# BAR30-SENSOR.net
KiCad netlist of a schematic drawn in EAGLE
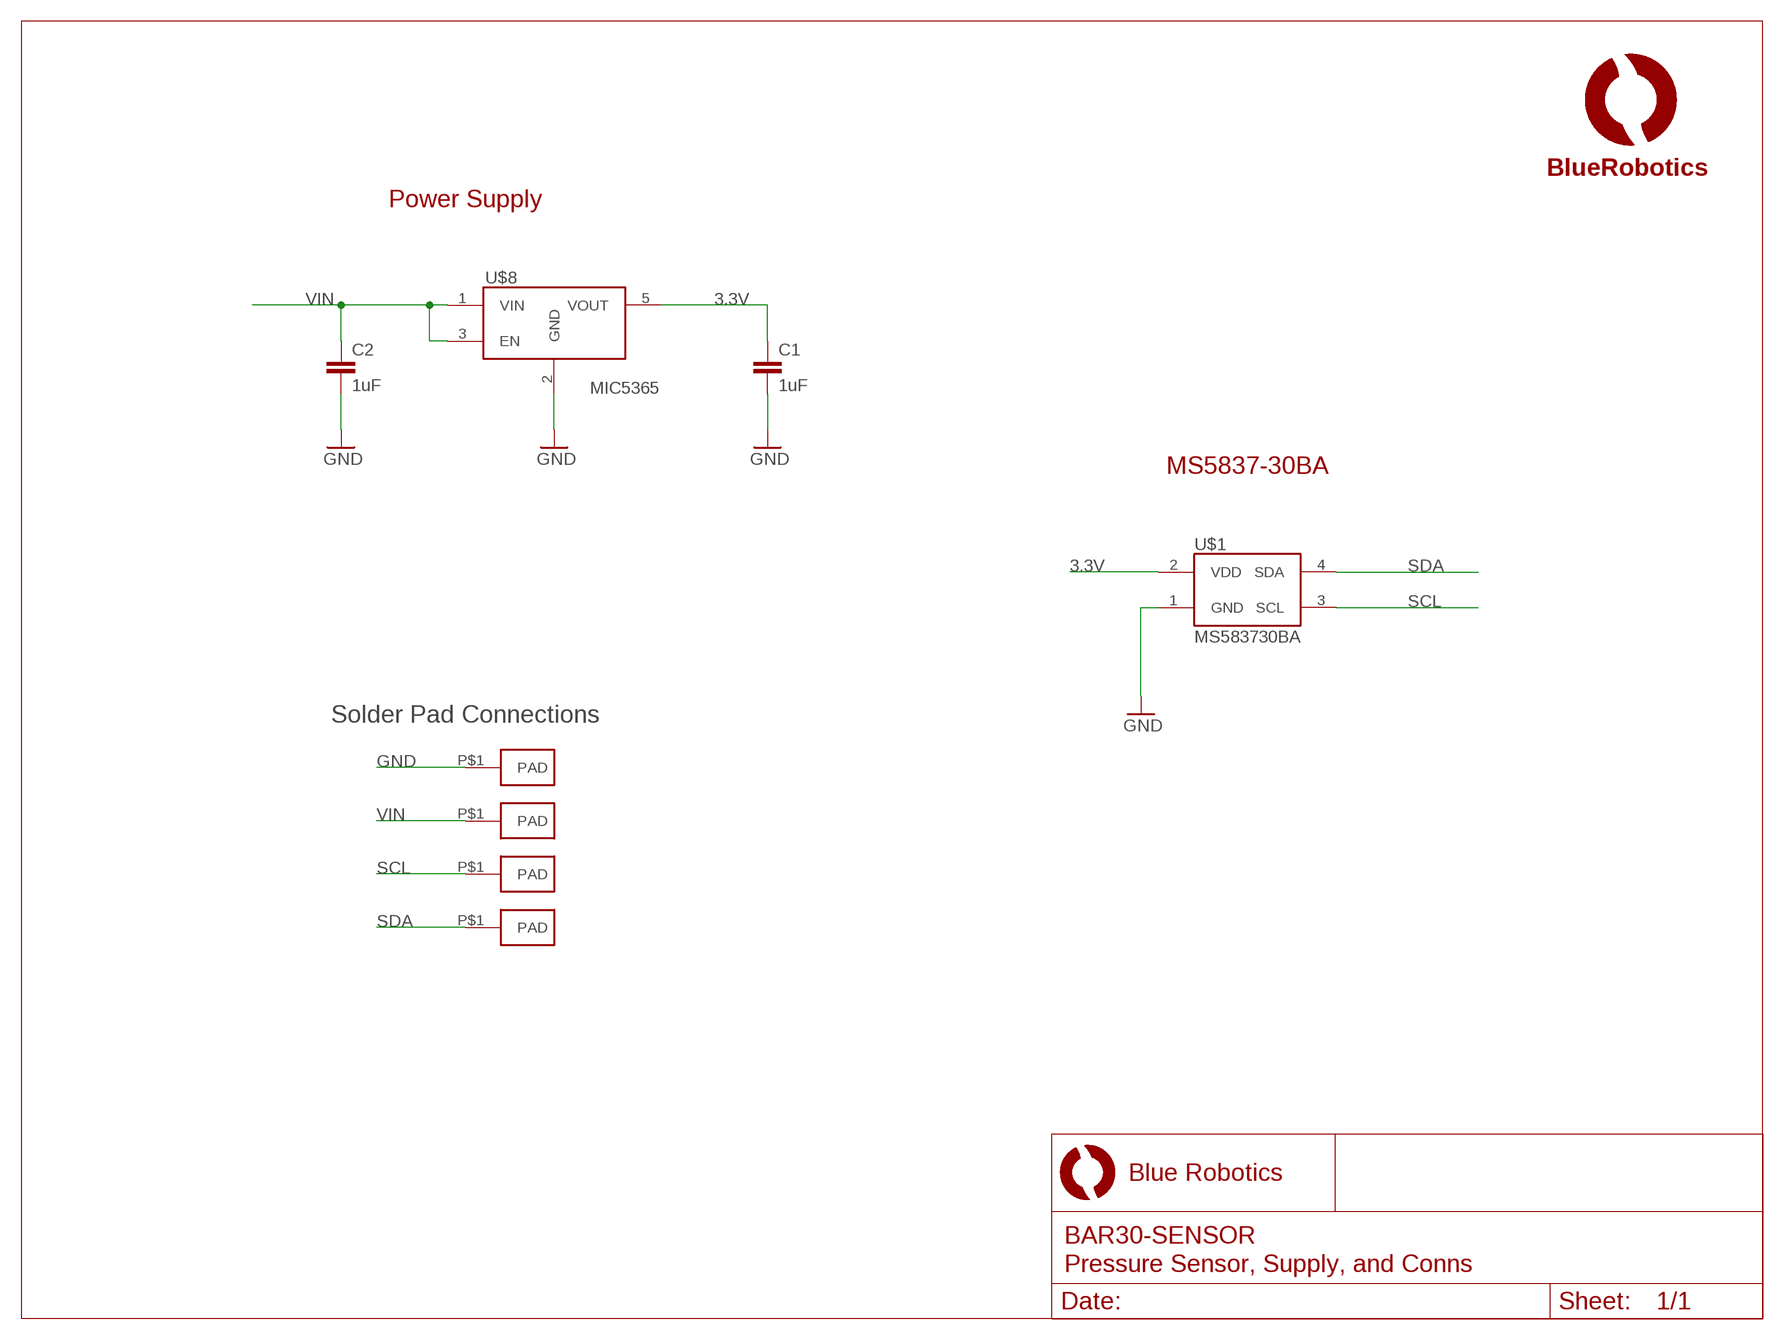
[diagram p0: schematic, sheet 1]

(export (version "E")
  (design (tool "Eeschema 10.0.6"))
  (components
    (comp (ref "C1")
      (value "1uF")
      (footprint "eagle-import:C0402")
      (libsource (lib "eagle-import") (part "C-EUC0402"))
    )
    (comp (ref "C2")
      (value "1uF")
      (footprint "eagle-import:C0402")
      (libsource (lib "eagle-import") (part "C-EUC0402"))
    )
    (comp (ref "U$1")
      (value "MS583730BA")
      (footprint "eagle-import:MS5837")
      (libsource (lib "eagle-import") (part "MS583730BA"))
    )
    (comp (ref "U$3")
      (value "PAD1.5X3MM")
      (footprint "eagle-import:PAD-1.5X3MM")
      (libsource (lib "eagle-import") (part "PAD1.5X3MM"))
    )
    (comp (ref "U$4")
      (value "PAD1.5X3MM")
      (footprint "eagle-import:PAD-1.5X3MM")
      (libsource (lib "eagle-import") (part "PAD1.5X3MM"))
    )
    (comp (ref "U$5")
      (value "PAD1.5X3MM")
      (footprint "eagle-import:PAD-1.5X3MM")
      (libsource (lib "eagle-import") (part "PAD1.5X3MM"))
    )
    (comp (ref "U$6")
      (value "PAD1.5X3MM")
      (footprint "eagle-import:PAD-1.5X3MM")
      (libsource (lib "eagle-import") (part "PAD1.5X3MM"))
    )
    (comp (ref "U$7")
      (value "LOGOBR-LOGO-S")
      (footprint "eagle-import:BR-LOGO-SMALL")
      (libsource (lib "eagle-import") (part "LOGOBR-LOGO-S"))
    )
    (comp (ref "U$8")
      (value "VREG-MIC5365")
      (footprint "eagle-import:SC70-5L")
      (libsource (lib "eagle-import") (part "VREG-MIC5365"))
    )
  )
  (nets
    (net (code "1") (name "/3.3V") (class "Default")
      (node (ref "C1") (pin "1") (pinfunction "1_1") (pintype "passive"))
      (node (ref "U$1") (pin "2") (pinfunction "VDD_2") (pintype "bidirectional"))
      (node (ref "U$8") (pin "5") (pinfunction "VOUT_5") (pintype "bidirectional"))
    )
    (net (code "2") (name "/SCL") (class "Default")
      (node (ref "U$1") (pin "3") (pinfunction "SCL_3") (pintype "bidirectional"))
      (node (ref "U$5") (pin "P$1") (pinfunction "PAD_P$1") (pintype "bidirectional"))
    )
    (net (code "3") (name "/SDA") (class "Default")
      (node (ref "U$1") (pin "4") (pinfunction "SDA_4") (pintype "bidirectional"))
      (node (ref "U$6") (pin "P$1") (pinfunction "PAD_P$1") (pintype "bidirectional"))
    )
    (net (code "4") (name "/VIN") (class "Default")
      (node (ref "C2") (pin "1") (pinfunction "1_1") (pintype "passive"))
      (node (ref "U$4") (pin "P$1") (pinfunction "PAD_P$1") (pintype "bidirectional"))
      (node (ref "U$8") (pin "1") (pinfunction "VIN_1") (pintype "bidirectional"))
      (node (ref "U$8") (pin "3") (pinfunction "EN_3") (pintype "bidirectional"))
    )
    (net (code "5") (name "GND") (class "Default")
      (node (ref "C1") (pin "2") (pinfunction "2_2") (pintype "passive"))
      (node (ref "C2") (pin "2") (pinfunction "2_2") (pintype "passive"))
      (node (ref "U$1") (pin "1") (pinfunction "GND_1") (pintype "bidirectional"))
      (node (ref "U$3") (pin "P$1") (pinfunction "PAD_P$1") (pintype "bidirectional"))
      (node (ref "U$8") (pin "2") (pinfunction "GND_2") (pintype "bidirectional"))
    )
  )
)
